# STM8S103F3P6.net
KiCad netlist of a schematic drawn in Altium Designer
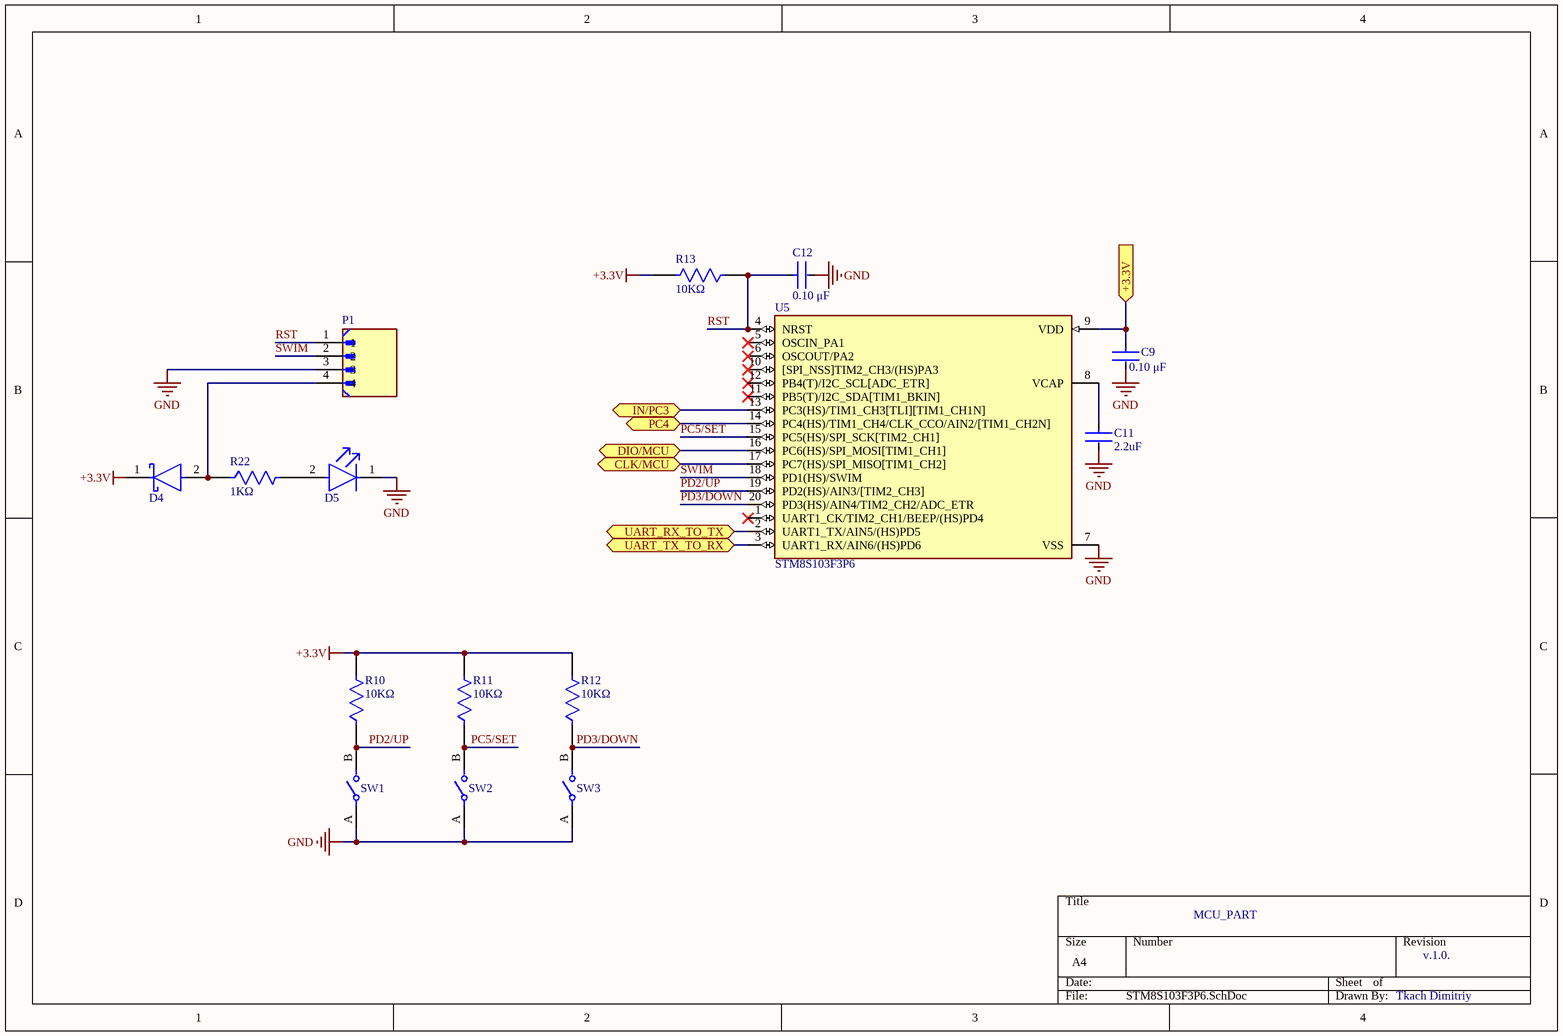
[diagram p0: STM8S103F3P6.SchDoc]

(export (version "E")
  (design (tool "Eeschema 10.0.6"))
  (components
    (comp (ref "C9")
      (value "C1206C104K5RACAUTO")
      (footprint "CAPC3216X18M")
      (description "CAP CER 0.1UF 50V X7R 1206")
      (fields
        (field (name "MANUFACTURER") "KEMET")
        (field (name "OCTOPART") "https://octopart.com/c1206c104k5racauto-kemet-12595586")
        (field (name "CAPACITANCE") "0.10 μF")
      )
      (libsource (lib "Internal_Lib_Thermostat_STM8") (part "CMP-03020-005759-1"))
    )
    (comp (ref "C11")
      (value "C1206C225K5RACAUTO")
      (footprint "CAPC3216X18M")
      (description "CAP CER 2.2UF 50V X7R 1206")
      (fields (field (name "TOLERANCE") "10%") (field (name "CAPACITANCE") "2.2uF"))
      (libsource (lib "Thermostat_Components") (part "CMP-03020-034660-1"))
    )
    (comp (ref "C12")
      (value "C1206C104K5RACAUTO")
      (footprint "CAPC3216X18M")
      (description "CAP CER 0.1UF 50V X7R 1206")
      (fields
        (field (name "MANUFACTURER") "KEMET")
        (field (name "OCTOPART") "https://octopart.com/c1206c104k5racauto-kemet-12595586")
        (field (name "CAPACITANCE") "0.10 μF")
      )
      (libsource (lib "Internal_Lib_Thermostat_STM8") (part "CMP-03020-005759-1"))
    )
    (comp (ref "D4")
      (value "1N5819HW-7-F")
      (footprint "FP-SOD123-MFG")
      (description "DIODE SCHOTTKY 40V 1A SOD123")
      (libsource (lib "Internal_Lib_Thermostat_STM8") (part "CMP-0303-00003-3"))
    )
    (comp (ref "D5")
      (value "LTST-C150KRKT")
      (footprint "FP-LTST-C150KRKT-MFG")
      (description "LED RED CLEAR 1206 SMD")
      (libsource (lib "Internal_Lib_Thermostat_STM8") (part "8706943c75ba83719d021d2fdc84c58"))
    )
    (comp (ref "P1")
      (value "61300411121")
      (footprint "WURTH_61300411121")
      (description "Connector Header Through Hole 4 position 0.100 (2.54mm)")
      (fields (field (name "MF") "WÃ¼rth Elektronik"))
      (libsource (lib "Internal_Lib_Thermostat_STM8") (part "61300411121"))
    )
    (comp (ref "R10")
      (value "CRGP1206F10K")
      (footprint "RESC3216X06M")
      (description "CRGP 1206 10K 1%")
      (fields
        (field (name "OCTOPART") "https://octopart.com/crgp1206f10k-te+connectivity-91018843")
        (field (name "TOLERANCE") "0.01")
        (field (name "RESISTANCE") "10KΩ")
      )
      (libsource (lib "Internal_Lib_Thermostat_STM8") (part "CMP-03211-004788-1"))
    )
    (comp (ref "R11")
      (value "CRGP1206F10K")
      (footprint "RESC3216X06M")
      (description "CRGP 1206 10K 1%")
      (fields
        (field (name "OCTOPART") "https://octopart.com/crgp1206f10k-te+connectivity-91018843")
        (field (name "TOLERANCE") "0.01")
        (field (name "RESISTANCE") "10KΩ")
      )
      (libsource (lib "Internal_Lib_Thermostat_STM8") (part "CMP-03211-004788-1"))
    )
    (comp (ref "R12")
      (value "CRGP1206F10K")
      (footprint "RESC3216X06M")
      (description "CRGP 1206 10K 1%")
      (fields
        (field (name "OCTOPART") "https://octopart.com/crgp1206f10k-te+connectivity-91018843")
        (field (name "TOLERANCE") "0.01")
        (field (name "RESISTANCE") "10KΩ")
      )
      (libsource (lib "Internal_Lib_Thermostat_STM8") (part "CMP-03211-004788-1"))
    )
    (comp (ref "R13")
      (value "CRGP1206F10K")
      (footprint "RESC3216X06M")
      (description "CRGP 1206 10K 1%")
      (fields
        (field (name "OCTOPART") "https://octopart.com/crgp1206f10k-te+connectivity-91018843")
        (field (name "TOLERANCE") "0.01")
        (field (name "RESISTANCE") "10KΩ")
      )
      (libsource (lib "Internal_Lib_Thermostat_STM8") (part "CMP-03211-004788-1"))
    )
    (comp (ref "R22")
      (value "1KΩ")
      (footprint "RESC3216X06M")
      (description "CRGCQ1206 1KΩ 0.25W 1% ±100ppm/°C 200V")
      (fields
        (field (name "MANUFACTURER") "TE Connectivity")
        (field (name "MANUFACTURER PART NUMBER") "CRGCQ1206F1K0")
      )
      (libsource (lib "Internal_Lib_Thermostat_STM8") (part "CMP-03211-006592-1"))
    )
    (comp (ref "SW1")
      (value "EVQ-QJJ05Q")
      (footprint "FP-EVQ-QJJ05Q-MFG")
      (description "EVQ-QJJ05Q Switch Tactile N.O. SPST Round Button PC Pins 0.005A 12VDC 0.8N Thru-Hole Radial T/R")
      (libsource (lib "Internal_Lib_Thermostat_STM8") (part "CMP-00287-56250562-1"))
    )
    (comp (ref "SW2")
      (value "EVQ-QJJ05Q")
      (footprint "FP-EVQ-QJJ05Q-MFG")
      (description "EVQ-QJJ05Q Switch Tactile N.O. SPST Round Button PC Pins 0.005A 12VDC 0.8N Thru-Hole Radial T/R")
      (libsource (lib "Internal_Lib_Thermostat_STM8") (part "CMP-00287-56250562-1"))
    )
    (comp (ref "SW3")
      (value "EVQ-QJJ05Q")
      (footprint "FP-EVQ-QJJ05Q-MFG")
      (description "EVQ-QJJ05Q Switch Tactile N.O. SPST Round Button PC Pins 0.005A 12VDC 0.8N Thru-Hole Radial T/R")
      (libsource (lib "Internal_Lib_Thermostat_STM8") (part "CMP-00287-56250562-1"))
    )
    (comp (ref "U5")
      (value "STM8S103F3P6")
      (footprint "SOP65P640X120-20N")
      (description "STM8 series Microcontroller IC 8-Bit 16MHz 8KB (8K x 8) FLASH 20-TSSOP")
      (fields (field (name "MF") "STMicroelectronics"))
      (libsource (lib "Internal_Lib_Thermostat_STM8") (part "STM8S103F3P6"))
    )
  )
  (nets
    (net (code "1") (name "+3.3V") (class "Default")
      (node (ref "C9") (pin "1") (pinfunction "1_1") (pintype "passive"))
      (node (ref "D4") (pin "1") (pinfunction "C_1") (pintype "passive"))
      (node (ref "R10") (pin "2") (pinfunction "2_2") (pintype "passive"))
      (node (ref "R11") (pin "2") (pinfunction "2_2") (pintype "passive"))
      (node (ref "R12") (pin "2") (pinfunction "2_2") (pintype "passive"))
      (node (ref "R13") (pin "2") (pinfunction "2_2") (pintype "passive"))
      (node (ref "U5") (pin "9") (pinfunction "VDD_9") (pintype "input"))
    )
    (net (code "2") (name "/CLK{slash}MCU") (class "Default")
      (node (ref "U5") (pin "17") (pinfunction "PC7(HS)/SPI_MISO[TIM1_CH2]_17") (pintype "bidirectional"))
    )
    (net (code "3") (name "/DIO{slash}MCU") (class "Default")
      (node (ref "U5") (pin "16") (pinfunction "PC6(HS)/SPI_MOSI[TIM1_CH1]_16") (pintype "bidirectional"))
    )
    (net (code "4") (name "/IN{slash}PC3") (class "Default")
      (node (ref "U5") (pin "13") (pinfunction "PC3(HS)/TIM1_CH3[TLI][TIM1_CH1N]_13") (pintype "bidirectional"))
    )
    (net (code "5") (name "/PC4") (class "Default")
      (node (ref "U5") (pin "14") (pinfunction "PC4(HS)/TIM1_CH4/CLK_CCO/AIN2/[TIM1_CH2N]_14") (pintype "bidirectional"))
    )
    (net (code "6") (name "/PC5{slash}SET") (class "Default")
      (node (ref "R11") (pin "1") (pinfunction "1_1") (pintype "passive"))
      (node (ref "SW2") (pin "B") (pinfunction "B_B") (pintype "passive"))
      (node (ref "U5") (pin "15") (pinfunction "PC5(HS)/SPI_SCK[TIM2_CH1]_15") (pintype "bidirectional"))
    )
    (net (code "7") (name "/PD2{slash}UP") (class "Default")
      (node (ref "R10") (pin "1") (pinfunction "1_1") (pintype "passive"))
      (node (ref "SW1") (pin "B") (pinfunction "B_B") (pintype "passive"))
      (node (ref "U5") (pin "19") (pinfunction "PD2(HS)/AIN3/[TIM2_CH3]_19") (pintype "bidirectional"))
    )
    (net (code "8") (name "/PD3{slash}DOWN") (class "Default")
      (node (ref "R12") (pin "1") (pinfunction "1_1") (pintype "passive"))
      (node (ref "SW3") (pin "B") (pinfunction "B_B") (pintype "passive"))
      (node (ref "U5") (pin "20") (pinfunction "PD3(HS)/AIN4/TIM2_CH2/ADC_ETR_20") (pintype "bidirectional"))
    )
    (net (code "9") (name "/RST") (class "Default")
      (node (ref "C12") (pin "1") (pinfunction "1_1") (pintype "passive"))
      (node (ref "P1") (pin "1") (pinfunction "1_1") (pintype "passive"))
      (node (ref "R13") (pin "1") (pinfunction "1_1") (pintype "passive"))
      (node (ref "U5") (pin "4") (pinfunction "NRST_4") (pintype "bidirectional"))
    )
    (net (code "10") (name "/SWIM") (class "Default")
      (node (ref "P1") (pin "2") (pinfunction "2_2") (pintype "passive"))
      (node (ref "U5") (pin "18") (pinfunction "PD1(HS)/SWIM_18") (pintype "bidirectional"))
    )
    (net (code "11") (name "/UART_RX_TO_TX") (class "Default")
      (node (ref "U5") (pin "2") (pinfunction "UART1_TX/AIN5/(HS)PD5_2") (pintype "bidirectional"))
    )
    (net (code "12") (name "/UART_TX_TO_RX") (class "Default")
      (node (ref "U5") (pin "3") (pinfunction "UART1_RX/AIN6/(HS)PD6_3") (pintype "bidirectional"))
    )
    (net (code "13") (name "GND") (class "Default")
      (node (ref "C11") (pin "2") (pinfunction "2_2") (pintype "passive"))
      (node (ref "C12") (pin "2") (pinfunction "2_2") (pintype "passive"))
      (node (ref "C9") (pin "2") (pinfunction "2_2") (pintype "passive"))
      (node (ref "D5") (pin "1") (pinfunction "C_1") (pintype "passive"))
      (node (ref "P1") (pin "3") (pinfunction "3_3") (pintype "passive"))
      (node (ref "SW1") (pin "A") (pinfunction "A_A") (pintype "passive"))
      (node (ref "SW2") (pin "A") (pinfunction "A_A") (pintype "passive"))
      (node (ref "SW3") (pin "A") (pinfunction "A_A") (pintype "passive"))
      (node (ref "U5") (pin "7") (pinfunction "VSS_7") (pintype "power_in"))
    )
    (net (code "14") (name "Net-(D4-A)") (class "Default")
      (node (ref "D4") (pin "2") (pinfunction "A_2") (pintype "passive"))
      (node (ref "P1") (pin "4") (pinfunction "4_4") (pintype "passive"))
      (node (ref "R22") (pin "1") (pinfunction "1_1") (pintype "passive"))
    )
    (net (code "15") (name "Net-(D5-A)") (class "Default")
      (node (ref "D5") (pin "2") (pinfunction "A_2") (pintype "passive"))
      (node (ref "R22") (pin "2") (pinfunction "2_2") (pintype "passive"))
    )
    (net (code "16") (name "Net-(U5-VCAP)") (class "Default")
      (node (ref "C11") (pin "1") (pinfunction "1_1") (pintype "passive"))
      (node (ref "U5") (pin "8") (pinfunction "VCAP_8") (pintype "passive"))
    )
    (net (code "17") (name "unconnected-(U5-OSCIN_PA1-Pad5)") (class "Default")
      (node (ref "U5") (pin "5") (pinfunction "OSCIN_PA1_5") (pintype "bidirectional+no_connect"))
    )
    (net (code "18") (name "unconnected-(U5-OSCOUT{slash}PA2-Pad6)") (class "Default")
      (node (ref "U5") (pin "6") (pinfunction "OSCOUT/PA2_6") (pintype "bidirectional+no_connect"))
    )
    (net (code "19") (name "unconnected-(U5-PB4(T){slash}I2C_SCL[ADC_ETR]-Pad12)") (class "Default")
      (node (ref "U5") (pin "12") (pinfunction "PB4(T)/I2C_SCL[ADC_ETR]_12") (pintype "bidirectional+no_connect"))
    )
    (net (code "20") (name "unconnected-(U5-PB5(T){slash}I2C_SDA[TIM1_BKIN]-Pad11)") (class "Default")
      (node (ref "U5") (pin "11") (pinfunction "PB5(T)/I2C_SDA[TIM1_BKIN]_11") (pintype "bidirectional+no_connect"))
    )
    (net (code "21") (name "unconnected-(U5-UART1_CK{slash}TIM2_CH1{slash}BEEP{slash}(HS)PD4-Pad1)") (class "Default")
      (node (ref "U5") (pin "1") (pinfunction "UART1_CK/TIM2_CH1/BEEP/(HS)PD4_1") (pintype "bidirectional+no_connect"))
    )
    (net (code "22") (name "unconnected-(U5-[SPI_NSS]TIM2_CH3{slash}(HS)PA3-Pad10)") (class "Default")
      (node (ref "U5") (pin "10") (pinfunction "[SPI_NSS]TIM2_CH3/(HS)PA3_10") (pintype "bidirectional+no_connect"))
    )
  )
)
